# Modular_Recon_Drone.net
KiCad netlist of a schematic drawn in EAGLE
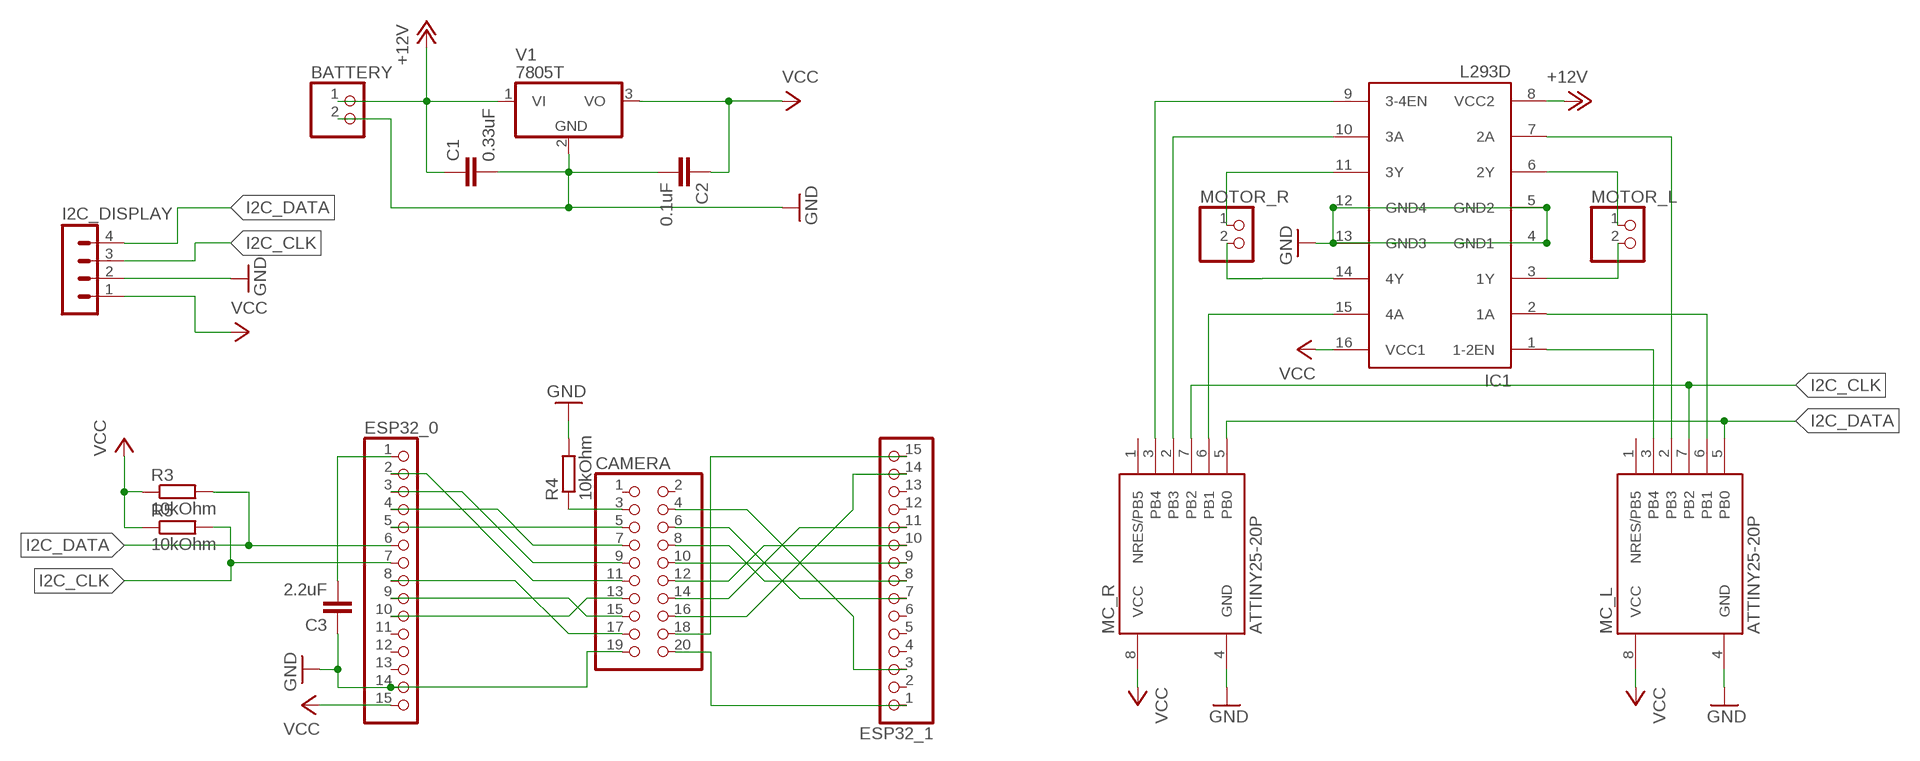
[diagram p0: schematic, sheet 1]

(export (version "E")
  (design (tool "Eeschema 10.0.6"))
  (components
    (comp (ref "BATTERY")
      (value "PINHD-1X2")
      (footprint "eagle-import:1X02")
      (libsource (lib "eagle-import") (part "PINHD-1X2"))
    )
    (comp (ref "C1")
      (value "0.33uF")
      (footprint "eagle-import:C025-050X050")
      (libsource (lib "eagle-import") (part "C-EU025-050X050"))
    )
    (comp (ref "C2")
      (value "0.1uF")
      (footprint "eagle-import:C025-050X050")
      (libsource (lib "eagle-import") (part "C-EU025-050X050"))
    )
    (comp (ref "C3")
      (value "2.2uF")
      (footprint "eagle-import:C025-050X050")
      (libsource (lib "eagle-import") (part "C-EU025-050X050"))
    )
    (comp (ref "CAMERA")
      (value "PINHD-2X10")
      (footprint "eagle-import:2X10")
      (libsource (lib "eagle-import") (part "PINHD-2X10"))
    )
    (comp (ref "ESP32_0")
      (value "PINHD-1X15")
      (footprint "eagle-import:1X15")
      (libsource (lib "eagle-import") (part "PINHD-1X15"))
    )
    (comp (ref "ESP32_1")
      (value "PINHD-1X15")
      (footprint "eagle-import:1X15")
      (libsource (lib "eagle-import") (part "PINHD-1X15"))
    )
    (comp (ref "I2C_DISPLAY")
      (value "MA04-1")
      (footprint "eagle-import:MA04-1")
      (libsource (lib "eagle-import") (part "MA04-1"))
    )
    (comp (ref "IC1")
      (value "L293D")
      (footprint "eagle-import:DIL16")
      (libsource (lib "eagle-import") (part "L293D"))
    )
    (comp (ref "MC_L")
      (value "ATTINY25-20P")
      (footprint "eagle-import:PDIP08_300MIL")
      (libsource (lib "eagle-import") (part "ATTINY25P-20"))
    )
    (comp (ref "MC_R")
      (value "ATTINY25-20P")
      (footprint "eagle-import:PDIP08_300MIL")
      (libsource (lib "eagle-import") (part "ATTINY25P-20"))
    )
    (comp (ref "MOTOR_L")
      (value "PINHD-1X2")
      (footprint "eagle-import:1X02")
      (libsource (lib "eagle-import") (part "PINHD-1X2"))
    )
    (comp (ref "MOTOR_R")
      (value "PINHD-1X2")
      (footprint "eagle-import:1X02")
      (libsource (lib "eagle-import") (part "PINHD-1X2"))
    )
    (comp (ref "R3")
      (value "10kOhm")
      (footprint "eagle-import:0204_5")
      (libsource (lib "eagle-import") (part "R-EU_0204/5"))
    )
    (comp (ref "R4")
      (value "10kOhm")
      (footprint "eagle-import:0204_5")
      (libsource (lib "eagle-import") (part "R-EU_0204/5"))
    )
    (comp (ref "R5")
      (value "10kOhm")
      (footprint "eagle-import:0204_5")
      (libsource (lib "eagle-import") (part "R-EU_0204/5"))
    )
    (comp (ref "V1")
      (value "7805T")
      (footprint "eagle-import:TO220H")
      (libsource (lib "eagle-import") (part "78T05"))
    )
  )
  (nets
    (net (code "1") (name "+12V") (class "Default")
      (node (ref "BATTERY") (pin "1") (pinfunction "1_1") (pintype "passive"))
      (node (ref "C1") (pin "1") (pinfunction "1_1") (pintype "passive"))
      (node (ref "IC1") (pin "8") (pinfunction "VCC2_8") (pintype "power_in"))
      (node (ref "V1") (pin "1") (pinfunction "VI_1") (pintype "input"))
    )
    (net (code "2") (name "GND") (class "Default")
      (node (ref "BATTERY") (pin "2") (pinfunction "2_2") (pintype "passive"))
      (node (ref "C1") (pin "2") (pinfunction "2_2") (pintype "passive"))
      (node (ref "C2") (pin "2") (pinfunction "2_2") (pintype "passive"))
      (node (ref "C3") (pin "1") (pinfunction "1_1") (pintype "passive"))
      (node (ref "CAMERA") (pin "19") (pinfunction "19_19") (pintype "passive"))
      (node (ref "ESP32_0") (pin "14") (pinfunction "14_14") (pintype "passive"))
      (node (ref "I2C_DISPLAY") (pin "2") (pinfunction "2_2") (pintype "passive"))
      (node (ref "IC1") (pin "12") (pinfunction "GND4_12") (pintype "power_in"))
      (node (ref "IC1") (pin "13") (pinfunction "GND3_13") (pintype "power_in"))
      (node (ref "IC1") (pin "4") (pinfunction "GND1_4") (pintype "power_in"))
      (node (ref "IC1") (pin "5") (pinfunction "GND2_5") (pintype "power_in"))
      (node (ref "MC_L") (pin "4") (pinfunction "GND_4") (pintype "power_in"))
      (node (ref "MC_R") (pin "4") (pinfunction "GND_4") (pintype "power_in"))
      (node (ref "R4") (pin "2") (pinfunction "2_2") (pintype "passive"))
      (node (ref "V1") (pin "2") (pinfunction "GND_2") (pintype "passive"))
    )
    (net (code "3") (name "I2C_CLK") (class "Default")
      (node (ref "ESP32_0") (pin "7") (pinfunction "7_7") (pintype "passive"))
      (node (ref "I2C_DISPLAY") (pin "3") (pinfunction "3_3") (pintype "passive"))
      (node (ref "MC_L") (pin "7") (pinfunction "PB2_7") (pintype "bidirectional"))
      (node (ref "MC_R") (pin "7") (pinfunction "PB2_7") (pintype "bidirectional"))
      (node (ref "R5") (pin "2") (pinfunction "2_2") (pintype "passive"))
    )
    (net (code "4") (name "I2C_DATA") (class "Default")
      (node (ref "ESP32_0") (pin "6") (pinfunction "6_6") (pintype "passive"))
      (node (ref "I2C_DISPLAY") (pin "4") (pinfunction "4_4") (pintype "passive"))
      (node (ref "MC_L") (pin "5") (pinfunction "PB0_5") (pintype "bidirectional"))
      (node (ref "MC_R") (pin "5") (pinfunction "PB0_5") (pintype "bidirectional"))
      (node (ref "R3") (pin "2") (pinfunction "2_2") (pintype "passive"))
    )
    (net (code "5") (name "Net-(C3-Pad2)") (class "Default")
      (node (ref "C3") (pin "2") (pinfunction "2_2") (pintype "passive"))
      (node (ref "ESP32_0") (pin "1") (pinfunction "1_1") (pintype "passive"))
    )
    (net (code "6") (name "Net-(CAMERA-Pad3)") (class "Default")
      (node (ref "CAMERA") (pin "3") (pinfunction "3_3") (pintype "passive"))
      (node (ref "R4") (pin "1") (pinfunction "1_1") (pintype "passive"))
    )
    (net (code "7") (name "Net-(CAMERA-Pad4)") (class "Default")
      (node (ref "CAMERA") (pin "4") (pinfunction "4_4") (pintype "passive"))
      (node (ref "ESP32_1") (pin "3") (pinfunction "3_3") (pintype "passive"))
    )
    (net (code "8") (name "Net-(CAMERA-Pad5)") (class "Default")
      (node (ref "CAMERA") (pin "5") (pinfunction "5_5") (pintype "passive"))
      (node (ref "ESP32_0") (pin "5") (pinfunction "5_5") (pintype "passive"))
    )
    (net (code "9") (name "Net-(CAMERA-Pad6)") (class "Default")
      (node (ref "CAMERA") (pin "6") (pinfunction "6_6") (pintype "passive"))
      (node (ref "ESP32_1") (pin "7") (pinfunction "7_7") (pintype "passive"))
    )
    (net (code "10") (name "Net-(CAMERA-Pad7)") (class "Default")
      (node (ref "CAMERA") (pin "7") (pinfunction "7_7") (pintype "passive"))
      (node (ref "ESP32_0") (pin "4") (pinfunction "4_4") (pintype "passive"))
    )
    (net (code "11") (name "Net-(CAMERA-Pad8)") (class "Default")
      (node (ref "CAMERA") (pin "8") (pinfunction "8_8") (pintype "passive"))
      (node (ref "ESP32_1") (pin "8") (pinfunction "8_8") (pintype "passive"))
    )
    (net (code "12") (name "Net-(CAMERA-Pad9)") (class "Default")
      (node (ref "CAMERA") (pin "9") (pinfunction "9_9") (pintype "passive"))
      (node (ref "ESP32_0") (pin "3") (pinfunction "3_3") (pintype "passive"))
    )
    (net (code "13") (name "Net-(CAMERA-Pad10)") (class "Default")
      (node (ref "CAMERA") (pin "10") (pinfunction "10_10") (pintype "passive"))
      (node (ref "ESP32_1") (pin "9") (pinfunction "9_9") (pintype "passive"))
    )
    (net (code "14") (name "Net-(CAMERA-Pad11)") (class "Default")
      (node (ref "CAMERA") (pin "11") (pinfunction "11_11") (pintype "passive"))
      (node (ref "ESP32_0") (pin "2") (pinfunction "2_2") (pintype "passive"))
    )
    (net (code "15") (name "Net-(CAMERA-Pad12)") (class "Default")
      (node (ref "CAMERA") (pin "12") (pinfunction "12_12") (pintype "passive"))
      (node (ref "ESP32_1") (pin "10") (pinfunction "10_10") (pintype "passive"))
    )
    (net (code "16") (name "Net-(CAMERA-Pad13)") (class "Default")
      (node (ref "CAMERA") (pin "13") (pinfunction "13_13") (pintype "passive"))
      (node (ref "ESP32_0") (pin "10") (pinfunction "10_10") (pintype "passive"))
    )
    (net (code "17") (name "Net-(CAMERA-Pad14)") (class "Default")
      (node (ref "CAMERA") (pin "14") (pinfunction "14_14") (pintype "passive"))
      (node (ref "ESP32_1") (pin "11") (pinfunction "11_11") (pintype "passive"))
    )
    (net (code "18") (name "Net-(CAMERA-Pad15)") (class "Default")
      (node (ref "CAMERA") (pin "15") (pinfunction "15_15") (pintype "passive"))
      (node (ref "ESP32_0") (pin "9") (pinfunction "9_9") (pintype "passive"))
    )
    (net (code "19") (name "Net-(CAMERA-Pad16)") (class "Default")
      (node (ref "CAMERA") (pin "16") (pinfunction "16_16") (pintype "passive"))
      (node (ref "ESP32_1") (pin "14") (pinfunction "14_14") (pintype "passive"))
    )
    (net (code "20") (name "Net-(CAMERA-Pad17)") (class "Default")
      (node (ref "CAMERA") (pin "17") (pinfunction "17_17") (pintype "passive"))
      (node (ref "ESP32_0") (pin "8") (pinfunction "8_8") (pintype "passive"))
    )
    (net (code "21") (name "Net-(CAMERA-Pad18)") (class "Default")
      (node (ref "CAMERA") (pin "18") (pinfunction "18_18") (pintype "passive"))
      (node (ref "ESP32_1") (pin "15") (pinfunction "15_15") (pintype "passive"))
    )
    (net (code "22") (name "Net-(CAMERA-Pad20)") (class "Default")
      (node (ref "CAMERA") (pin "20") (pinfunction "20_20") (pintype "passive"))
      (node (ref "ESP32_1") (pin "1") (pinfunction "1_1") (pintype "passive"))
    )
    (net (code "23") (name "Net-(IC1-1-2EN)") (class "Default")
      (node (ref "IC1") (pin "1") (pinfunction "1-2EN_1") (pintype "input"))
      (node (ref "MC_L") (pin "3") (pinfunction "PB4_3") (pintype "bidirectional"))
    )
    (net (code "24") (name "Net-(IC1-1A)") (class "Default")
      (node (ref "IC1") (pin "2") (pinfunction "1A_2") (pintype "input"))
      (node (ref "MC_L") (pin "6") (pinfunction "PB1_6") (pintype "bidirectional"))
    )
    (net (code "25") (name "Net-(IC1-1Y)") (class "Default")
      (node (ref "IC1") (pin "3") (pinfunction "1Y_3") (pintype "output"))
      (node (ref "MOTOR_L") (pin "2") (pinfunction "2_2") (pintype "passive"))
    )
    (net (code "26") (name "Net-(IC1-2A)") (class "Default")
      (node (ref "IC1") (pin "7") (pinfunction "2A_7") (pintype "input"))
      (node (ref "MC_L") (pin "2") (pinfunction "PB3_2") (pintype "bidirectional"))
    )
    (net (code "27") (name "Net-(IC1-2Y)") (class "Default")
      (node (ref "IC1") (pin "6") (pinfunction "2Y_6") (pintype "output"))
      (node (ref "MOTOR_L") (pin "1") (pinfunction "1_1") (pintype "passive"))
    )
    (net (code "28") (name "Net-(IC1-3-4EN)") (class "Default")
      (node (ref "IC1") (pin "9") (pinfunction "3-4EN_9") (pintype "input"))
      (node (ref "MC_R") (pin "3") (pinfunction "PB4_3") (pintype "bidirectional"))
    )
    (net (code "29") (name "Net-(IC1-3A)") (class "Default")
      (node (ref "IC1") (pin "10") (pinfunction "3A_10") (pintype "input"))
      (node (ref "MC_R") (pin "2") (pinfunction "PB3_2") (pintype "bidirectional"))
    )
    (net (code "30") (name "Net-(IC1-3Y)") (class "Default")
      (node (ref "IC1") (pin "11") (pinfunction "3Y_11") (pintype "output"))
      (node (ref "MOTOR_R") (pin "1") (pinfunction "1_1") (pintype "passive"))
    )
    (net (code "31") (name "Net-(IC1-4A)") (class "Default")
      (node (ref "IC1") (pin "15") (pinfunction "4A_15") (pintype "input"))
      (node (ref "MC_R") (pin "6") (pinfunction "PB1_6") (pintype "bidirectional"))
    )
    (net (code "32") (name "Net-(IC1-4Y)") (class "Default")
      (node (ref "IC1") (pin "14") (pinfunction "4Y_14") (pintype "output"))
      (node (ref "MOTOR_R") (pin "2") (pinfunction "2_2") (pintype "passive"))
    )
    (net (code "33") (name "VCC") (class "Default")
      (node (ref "C2") (pin "1") (pinfunction "1_1") (pintype "passive"))
      (node (ref "ESP32_0") (pin "15") (pinfunction "15_15") (pintype "passive"))
      (node (ref "I2C_DISPLAY") (pin "1") (pinfunction "1_1") (pintype "passive"))
      (node (ref "IC1") (pin "16") (pinfunction "VCC1_16") (pintype "power_in"))
      (node (ref "MC_L") (pin "8") (pinfunction "VCC_8") (pintype "power_in"))
      (node (ref "MC_R") (pin "8") (pinfunction "VCC_8") (pintype "power_in"))
      (node (ref "R3") (pin "1") (pinfunction "1_1") (pintype "passive"))
      (node (ref "R5") (pin "1") (pinfunction "1_1") (pintype "passive"))
      (node (ref "V1") (pin "3") (pinfunction "VO_3") (pintype "passive"))
    )
    (net (code "34") (name "unconnected-(CAMERA-Pad1)") (class "Default")
      (node (ref "CAMERA") (pin "1") (pinfunction "1_1") (pintype "passive"))
    )
    (net (code "35") (name "unconnected-(CAMERA-Pad2)") (class "Default")
      (node (ref "CAMERA") (pin "2") (pinfunction "2_2") (pintype "passive"))
    )
    (net (code "36") (name "unconnected-(ESP32_0-Pad11)") (class "Default")
      (node (ref "ESP32_0") (pin "11") (pinfunction "11_11") (pintype "passive"))
    )
    (net (code "37") (name "unconnected-(ESP32_0-Pad12)") (class "Default")
      (node (ref "ESP32_0") (pin "12") (pinfunction "12_12") (pintype "passive"))
    )
    (net (code "38") (name "unconnected-(ESP32_0-Pad13)") (class "Default")
      (node (ref "ESP32_0") (pin "13") (pinfunction "13_13") (pintype "passive"))
    )
    (net (code "39") (name "unconnected-(ESP32_1-Pad2)") (class "Default")
      (node (ref "ESP32_1") (pin "2") (pinfunction "2_2") (pintype "passive"))
    )
    (net (code "40") (name "unconnected-(ESP32_1-Pad4)") (class "Default")
      (node (ref "ESP32_1") (pin "4") (pinfunction "4_4") (pintype "passive"))
    )
    (net (code "41") (name "unconnected-(ESP32_1-Pad5)") (class "Default")
      (node (ref "ESP32_1") (pin "5") (pinfunction "5_5") (pintype "passive"))
    )
    (net (code "42") (name "unconnected-(ESP32_1-Pad6)") (class "Default")
      (node (ref "ESP32_1") (pin "6") (pinfunction "6_6") (pintype "passive"))
    )
    (net (code "43") (name "unconnected-(ESP32_1-Pad12)") (class "Default")
      (node (ref "ESP32_1") (pin "12") (pinfunction "12_12") (pintype "passive"))
    )
    (net (code "44") (name "unconnected-(ESP32_1-Pad13)") (class "Default")
      (node (ref "ESP32_1") (pin "13") (pinfunction "13_13") (pintype "passive"))
    )
    (net (code "45") (name "unconnected-(MC_L-NRES{slash}PB5-Pad1)") (class "Default")
      (node (ref "MC_L") (pin "1") (pinfunction "NRES/PB5_1") (pintype "bidirectional"))
    )
    (net (code "46") (name "unconnected-(MC_R-NRES{slash}PB5-Pad1)") (class "Default")
      (node (ref "MC_R") (pin "1") (pinfunction "NRES/PB5_1") (pintype "bidirectional"))
    )
  )
)
